# FPGA_QDRII.net
KiCad netlist of a schematic drawn in Altium Designer
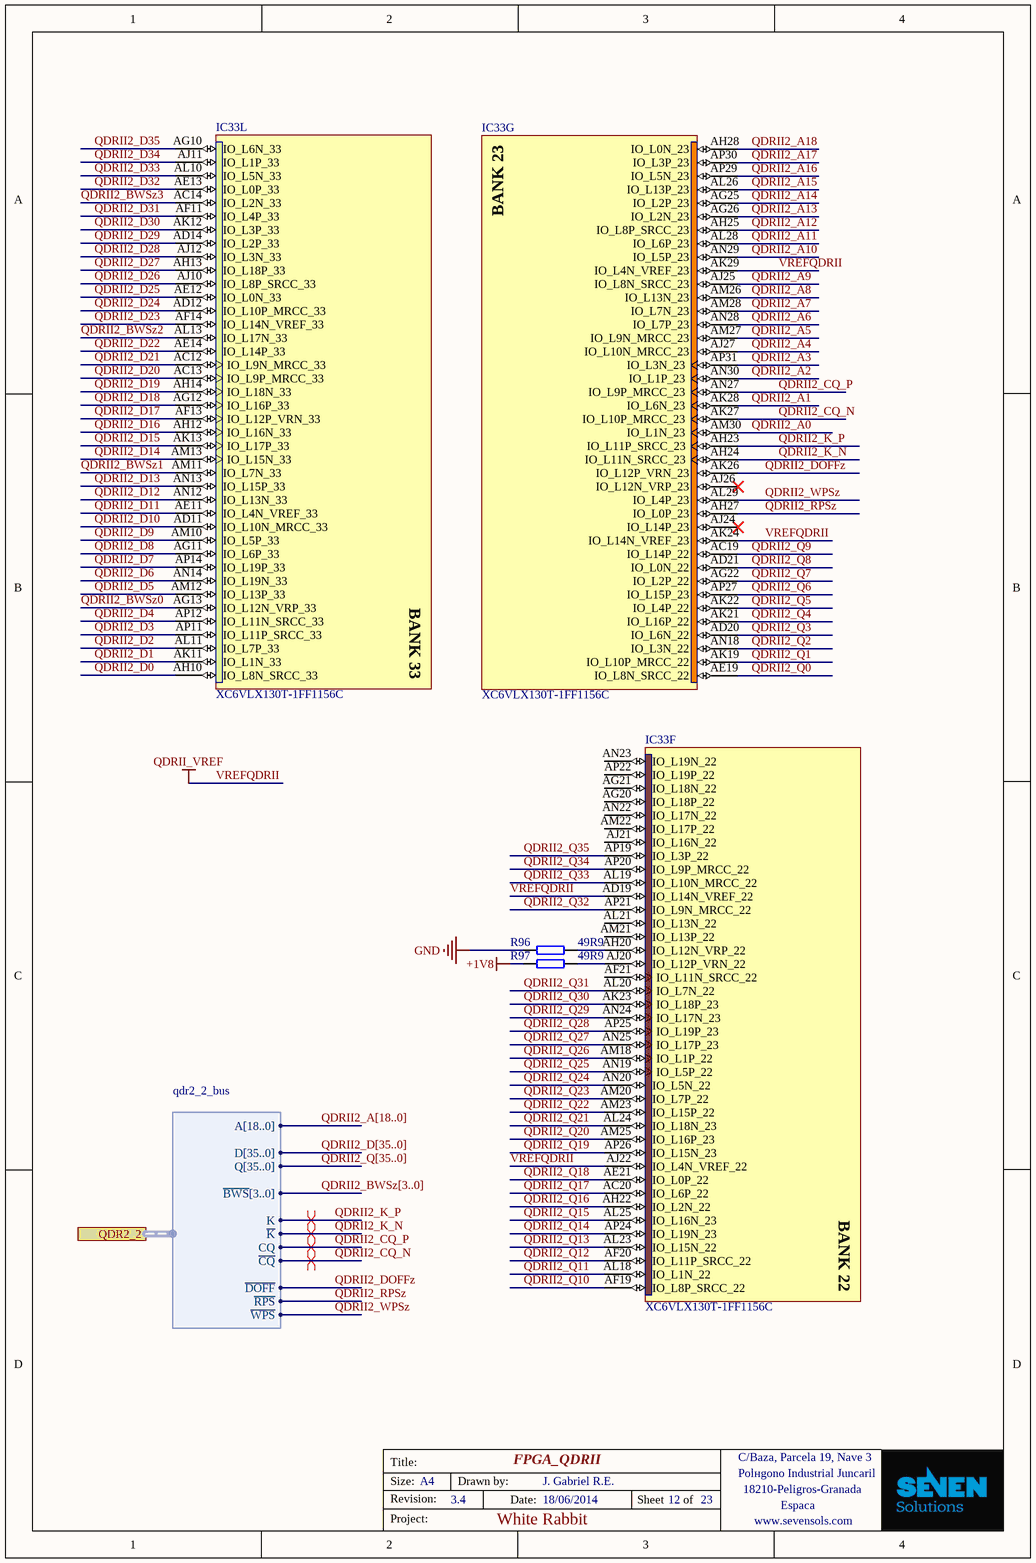
[diagram p0: FPGA_QDRII.SchDoc]

(export (version "E")
  (design (tool "Eeschema 10.0.6"))
  (components
    (comp (ref "IC33")
      (value "XC6VLX130T-1FF1156C")
      (footprint "FF1156")
      (fields (field (name "PUBLISHER") "Altium Limited"))
      (libsource (lib "Xilinx Virtex-6") (part "XC6VLX130T-1FF1156C"))
    )
    (comp (ref "R96")
      (value "49R9")
      (footprint "0402")
      (description "SMD Resistor")
      (fields (field (name "TOLERANCE") "±1%") (field (name "Comment") "49R9 (not mounted)"))
      (libsource (lib "wr_switch") (part "RES_SMD"))
    )
    (comp (ref "R97")
      (value "49R9")
      (footprint "0402")
      (description "SMD Resistor")
      (fields (field (name "TOLERANCE") "±1%") (field (name "Comment") "49R9 (not mounted)"))
      (libsource (lib "wr_switch") (part "RES_SMD"))
    )
  )
  (nets
    (net (code "2") (name "+1V8") (class "Default")
      (node (ref "R97") (pin "2") (pinfunction "2_2") (pintype "passive"))
    )
    (net (code "4") (name "/QDRII2_A0") (class "Default")
      (node (ref "IC33") (pin "AM30") (pinfunction "IO_L1N_23_AM30") (pintype "bidirectional"))
    )
    (net (code "5") (name "/QDRII2_A1") (class "Default")
      (node (ref "IC33") (pin "AK28") (pinfunction "IO_L6N_23_AK28") (pintype "bidirectional"))
    )
    (net (code "6") (name "/QDRII2_A2") (class "Default")
      (node (ref "IC33") (pin "AN30") (pinfunction "IO_L1P_23_AN30") (pintype "bidirectional"))
    )
    (net (code "7") (name "/QDRII2_A3") (class "Default")
      (node (ref "IC33") (pin "AP31") (pinfunction "IO_L3N_23_AP31") (pintype "bidirectional"))
    )
    (net (code "8") (name "/QDRII2_A4") (class "Default")
      (node (ref "IC33") (pin "AJ27") (pinfunction "IO_L10N_MRCC_23_AJ27") (pintype "bidirectional"))
    )
    (net (code "9") (name "/QDRII2_A5") (class "Default")
      (node (ref "IC33") (pin "AM27") (pinfunction "IO_L9N_MRCC_23_AM27") (pintype "bidirectional"))
    )
    (net (code "10") (name "/QDRII2_A6") (class "Default")
      (node (ref "IC33") (pin "AN28") (pinfunction "IO_L7P_23_AN28") (pintype "bidirectional"))
    )
    (net (code "11") (name "/QDRII2_A7") (class "Default")
      (node (ref "IC33") (pin "AM28") (pinfunction "IO_L7N_23_AM28") (pintype "bidirectional"))
    )
    (net (code "12") (name "/QDRII2_A8") (class "Default")
      (node (ref "IC33") (pin "AM26") (pinfunction "IO_L13N_23_AM26") (pintype "bidirectional"))
    )
    (net (code "13") (name "/QDRII2_A9") (class "Default")
      (node (ref "IC33") (pin "AJ25") (pinfunction "IO_L8N_SRCC_23_AJ25") (pintype "bidirectional"))
    )
    (net (code "14") (name "/QDRII2_A10") (class "Default")
      (node (ref "IC33") (pin "AN29") (pinfunction "IO_L5P_23_AN29") (pintype "bidirectional"))
    )
    (net (code "15") (name "/QDRII2_A11") (class "Default")
      (node (ref "IC33") (pin "AL28") (pinfunction "IO_L6P_23_AL28") (pintype "bidirectional"))
    )
    (net (code "16") (name "/QDRII2_A12") (class "Default")
      (node (ref "IC33") (pin "AH25") (pinfunction "IO_L8P_SRCC_23_AH25") (pintype "bidirectional"))
    )
    (net (code "17") (name "/QDRII2_A13") (class "Default")
      (node (ref "IC33") (pin "AG26") (pinfunction "IO_L2N_23_AG26") (pintype "bidirectional"))
    )
    (net (code "18") (name "/QDRII2_A14") (class "Default")
      (node (ref "IC33") (pin "AG25") (pinfunction "IO_L2P_23_AG25") (pintype "bidirectional"))
    )
    (net (code "19") (name "/QDRII2_A15") (class "Default")
      (node (ref "IC33") (pin "AL26") (pinfunction "IO_L13P_23_AL26") (pintype "bidirectional"))
    )
    (net (code "20") (name "/QDRII2_A16") (class "Default")
      (node (ref "IC33") (pin "AP29") (pinfunction "IO_L5N_23_AP29") (pintype "bidirectional"))
    )
    (net (code "21") (name "/QDRII2_A17") (class "Default")
      (node (ref "IC33") (pin "AP30") (pinfunction "IO_L3P_23_AP30") (pintype "bidirectional"))
    )
    (net (code "22") (name "/QDRII2_A18") (class "Default")
      (node (ref "IC33") (pin "AH28") (pinfunction "IO_L0N_23_AH28") (pintype "bidirectional"))
    )
    (net (code "24") (name "/QDRII2_BWSz0") (class "Default")
      (node (ref "IC33") (pin "AG13") (pinfunction "IO_L12N_VRP_33_AG13") (pintype "bidirectional"))
    )
    (net (code "25") (name "/QDRII2_BWSz1") (class "Default")
      (node (ref "IC33") (pin "AM11") (pinfunction "IO_L7N_33_AM11") (pintype "bidirectional"))
    )
    (net (code "26") (name "/QDRII2_BWSz2") (class "Default")
      (node (ref "IC33") (pin "AL13") (pinfunction "IO_L17N_33_AL13") (pintype "bidirectional"))
    )
    (net (code "27") (name "/QDRII2_BWSz3") (class "Default")
      (node (ref "IC33") (pin "AC14") (pinfunction "IO_L2N_33_AC14") (pintype "bidirectional"))
    )
    (net (code "28") (name "/QDRII2_CQ_N") (class "Default")
      (node (ref "IC33") (pin "AK27") (pinfunction "IO_L10P_MRCC_23_AK27") (pintype "bidirectional"))
    )
    (net (code "29") (name "/QDRII2_CQ_P") (class "Default")
      (node (ref "IC33") (pin "AN27") (pinfunction "IO_L9P_MRCC_23_AN27") (pintype "bidirectional"))
    )
    (net (code "30") (name "/QDRII2_D0") (class "Default")
      (node (ref "IC33") (pin "AH10") (pinfunction "IO_L8N_SRCC_33_AH10") (pintype "bidirectional"))
    )
    (net (code "31") (name "/QDRII2_D1") (class "Default")
      (node (ref "IC33") (pin "AK11") (pinfunction "IO_L1N_33_AK11") (pintype "bidirectional"))
    )
    (net (code "32") (name "/QDRII2_D2") (class "Default")
      (node (ref "IC33") (pin "AL11") (pinfunction "IO_L7P_33_AL11") (pintype "bidirectional"))
    )
    (net (code "33") (name "/QDRII2_D3") (class "Default")
      (node (ref "IC33") (pin "AP11") (pinfunction "IO_L11P_SRCC_33_AP11") (pintype "bidirectional"))
    )
    (net (code "34") (name "/QDRII2_D4") (class "Default")
      (node (ref "IC33") (pin "AP12") (pinfunction "IO_L11N_SRCC_33_AP12") (pintype "bidirectional"))
    )
    (net (code "35") (name "/QDRII2_D5") (class "Default")
      (node (ref "IC33") (pin "AM12") (pinfunction "IO_L13P_33_AM12") (pintype "bidirectional"))
    )
    (net (code "36") (name "/QDRII2_D6") (class "Default")
      (node (ref "IC33") (pin "AN14") (pinfunction "IO_L19N_33_AN14") (pintype "bidirectional"))
    )
    (net (code "37") (name "/QDRII2_D7") (class "Default")
      (node (ref "IC33") (pin "AP14") (pinfunction "IO_L19P_33_AP14") (pintype "bidirectional"))
    )
    (net (code "38") (name "/QDRII2_D8") (class "Default")
      (node (ref "IC33") (pin "AG11") (pinfunction "IO_L6P_33_AG11") (pintype "bidirectional"))
    )
    (net (code "39") (name "/QDRII2_D9") (class "Default")
      (node (ref "IC33") (pin "AM10") (pinfunction "IO_L5P_33_AM10") (pintype "bidirectional"))
    )
    (net (code "40") (name "/QDRII2_D10") (class "Default")
      (node (ref "IC33") (pin "AD11") (pinfunction "IO_L10N_MRCC_33_AD11") (pintype "bidirectional"))
    )
    (net (code "41") (name "/QDRII2_D11") (class "Default")
      (node (ref "IC33") (pin "AE11") (pinfunction "IO_L4N_VREF_33_AE11") (pintype "bidirectional"))
    )
    (net (code "42") (name "/QDRII2_D12") (class "Default")
      (node (ref "IC33") (pin "AN12") (pinfunction "IO_L13N_33_AN12") (pintype "bidirectional"))
    )
    (net (code "43") (name "/QDRII2_D13") (class "Default")
      (node (ref "IC33") (pin "AN13") (pinfunction "IO_L15P_33_AN13") (pintype "bidirectional"))
    )
    (net (code "44") (name "/QDRII2_D14") (class "Default")
      (node (ref "IC33") (pin "AM13") (pinfunction "IO_L15N_33_AM13") (pintype "bidirectional"))
    )
    (net (code "45") (name "/QDRII2_D15") (class "Default")
      (node (ref "IC33") (pin "AK13") (pinfunction "IO_L17P_33_AK13") (pintype "bidirectional"))
    )
    (net (code "46") (name "/QDRII2_D16") (class "Default")
      (node (ref "IC33") (pin "AH12") (pinfunction "IO_L16N_33_AH12") (pintype "bidirectional"))
    )
    (net (code "47") (name "/QDRII2_D17") (class "Default")
      (node (ref "IC33") (pin "AF13") (pinfunction "IO_L12P_VRN_33_AF13") (pintype "bidirectional"))
    )
    (net (code "48") (name "/QDRII2_D18") (class "Default")
      (node (ref "IC33") (pin "AG12") (pinfunction "IO_L16P_33_AG12") (pintype "bidirectional"))
    )
    (net (code "49") (name "/QDRII2_D19") (class "Default")
      (node (ref "IC33") (pin "AH14") (pinfunction "IO_L18N_33_AH14") (pintype "bidirectional"))
    )
    (net (code "50") (name "/QDRII2_D20") (class "Default")
      (node (ref "IC33") (pin "AC13") (pinfunction "IO_L9P_MRCC_33_AC13") (pintype "bidirectional"))
    )
    (net (code "51") (name "/QDRII2_D21") (class "Default")
      (node (ref "IC33") (pin "AC12") (pinfunction "IO_L9N_MRCC_33_AC12") (pintype "bidirectional"))
    )
    (net (code "52") (name "/QDRII2_D22") (class "Default")
      (node (ref "IC33") (pin "AE14") (pinfunction "IO_L14P_33_AE14") (pintype "bidirectional"))
    )
    (net (code "53") (name "/QDRII2_D23") (class "Default")
      (node (ref "IC33") (pin "AF14") (pinfunction "IO_L14N_VREF_33_AF14") (pintype "bidirectional"))
    )
    (net (code "54") (name "/QDRII2_D24") (class "Default")
      (node (ref "IC33") (pin "AD12") (pinfunction "IO_L10P_MRCC_33_AD12") (pintype "bidirectional"))
    )
    (net (code "55") (name "/QDRII2_D25") (class "Default")
      (node (ref "IC33") (pin "AE12") (pinfunction "IO_L0N_33_AE12") (pintype "bidirectional"))
    )
    (net (code "56") (name "/QDRII2_D26") (class "Default")
      (node (ref "IC33") (pin "AJ10") (pinfunction "IO_L8P_SRCC_33_AJ10") (pintype "bidirectional"))
    )
    (net (code "57") (name "/QDRII2_D27") (class "Default")
      (node (ref "IC33") (pin "AH13") (pinfunction "IO_L18P_33_AH13") (pintype "bidirectional"))
    )
    (net (code "58") (name "/QDRII2_D28") (class "Default")
      (node (ref "IC33") (pin "AJ12") (pinfunction "IO_L3N_33_AJ12") (pintype "bidirectional"))
    )
    (net (code "59") (name "/QDRII2_D29") (class "Default")
      (node (ref "IC33") (pin "AD14") (pinfunction "IO_L2P_33_AD14") (pintype "bidirectional"))
    )
    (net (code "60") (name "/QDRII2_D30") (class "Default")
      (node (ref "IC33") (pin "AK12") (pinfunction "IO_L3P_33_AK12") (pintype "bidirectional"))
    )
    (net (code "61") (name "/QDRII2_D31") (class "Default")
      (node (ref "IC33") (pin "AF11") (pinfunction "IO_L4P_33_AF11") (pintype "bidirectional"))
    )
    (net (code "62") (name "/QDRII2_D32") (class "Default")
      (node (ref "IC33") (pin "AE13") (pinfunction "IO_L0P_33_AE13") (pintype "bidirectional"))
    )
    (net (code "63") (name "/QDRII2_D33") (class "Default")
      (node (ref "IC33") (pin "AL10") (pinfunction "IO_L5N_33_AL10") (pintype "bidirectional"))
    )
    (net (code "64") (name "/QDRII2_D34") (class "Default")
      (node (ref "IC33") (pin "AJ11") (pinfunction "IO_L1P_33_AJ11") (pintype "bidirectional"))
    )
    (net (code "65") (name "/QDRII2_D35") (class "Default")
      (node (ref "IC33") (pin "AG10") (pinfunction "IO_L6N_33_AG10") (pintype "bidirectional"))
    )
    (net (code "66") (name "/QDRII2_DOFFz") (class "Default")
      (node (ref "IC33") (pin "AK26") (pinfunction "IO_L12P_VRN_23_AK26") (pintype "bidirectional"))
    )
    (net (code "68") (name "/QDRII2_K_N") (class "Default")
      (node (ref "IC33") (pin "AH24") (pinfunction "IO_L11N_SRCC_23_AH24") (pintype "bidirectional"))
    )
    (net (code "69") (name "/QDRII2_K_P") (class "Default")
      (node (ref "IC33") (pin "AH23") (pinfunction "IO_L11P_SRCC_23_AH23") (pintype "bidirectional"))
    )
    (net (code "70") (name "/QDRII2_Q0") (class "Default")
      (node (ref "IC33") (pin "AE19") (pinfunction "IO_L8N_SRCC_22_AE19") (pintype "bidirectional"))
    )
    (net (code "71") (name "/QDRII2_Q1") (class "Default")
      (node (ref "IC33") (pin "AK19") (pinfunction "IO_L10P_MRCC_22_AK19") (pintype "bidirectional"))
    )
    (net (code "72") (name "/QDRII2_Q2") (class "Default")
      (node (ref "IC33") (pin "AN18") (pinfunction "IO_L3N_22_AN18") (pintype "bidirectional"))
    )
    (net (code "73") (name "/QDRII2_Q3") (class "Default")
      (node (ref "IC33") (pin "AD20") (pinfunction "IO_L6N_22_AD20") (pintype "bidirectional"))
    )
    (net (code "74") (name "/QDRII2_Q4") (class "Default")
      (node (ref "IC33") (pin "AK21") (pinfunction "IO_L16P_22_AK21") (pintype "bidirectional"))
    )
    (net (code "75") (name "/QDRII2_Q5") (class "Default")
      (node (ref "IC33") (pin "AK22") (pinfunction "IO_L4P_22_AK22") (pintype "bidirectional"))
    )
    (net (code "76") (name "/QDRII2_Q6") (class "Default")
      (node (ref "IC33") (pin "AP27") (pinfunction "IO_L15P_23_AP27") (pintype "bidirectional"))
    )
    (net (code "77") (name "/QDRII2_Q7") (class "Default")
      (node (ref "IC33") (pin "AG22") (pinfunction "IO_L2P_22_AG22") (pintype "bidirectional"))
    )
    (net (code "78") (name "/QDRII2_Q8") (class "Default")
      (node (ref "IC33") (pin "AD21") (pinfunction "IO_L0N_22_AD21") (pintype "bidirectional"))
    )
    (net (code "79") (name "/QDRII2_Q9") (class "Default")
      (node (ref "IC33") (pin "AC19") (pinfunction "IO_L14P_22_AC19") (pintype "bidirectional"))
    )
    (net (code "80") (name "/QDRII2_Q10") (class "Default")
      (node (ref "IC33") (pin "AF19") (pinfunction "IO_L8P_SRCC_22_AF19") (pintype "bidirectional"))
    )
    (net (code "81") (name "/QDRII2_Q11") (class "Default")
      (node (ref "IC33") (pin "AL18") (pinfunction "IO_L1N_22_AL18") (pintype "bidirectional"))
    )
    (net (code "82") (name "/QDRII2_Q12") (class "Default")
      (node (ref "IC33") (pin "AF20") (pinfunction "IO_L11P_SRCC_22_AF20") (pintype "bidirectional"))
    )
    (net (code "83") (name "/QDRII2_Q13") (class "Default")
      (node (ref "IC33") (pin "AL23") (pinfunction "IO_L15N_22_AL23") (pintype "bidirectional"))
    )
    (net (code "84") (name "/QDRII2_Q14") (class "Default")
      (node (ref "IC33") (pin "AP24") (pinfunction "IO_L19N_23_AP24") (pintype "bidirectional"))
    )
    (net (code "85") (name "/QDRII2_Q15") (class "Default")
      (node (ref "IC33") (pin "AL25") (pinfunction "IO_L16N_23_AL25") (pintype "bidirectional"))
    )
    (net (code "86") (name "/QDRII2_Q16") (class "Default")
      (node (ref "IC33") (pin "AH22") (pinfunction "IO_L2N_22_AH22") (pintype "bidirectional"))
    )
    (net (code "87") (name "/QDRII2_Q17") (class "Default")
      (node (ref "IC33") (pin "AC20") (pinfunction "IO_L6P_22_AC20") (pintype "bidirectional"))
    )
    (net (code "88") (name "/QDRII2_Q18") (class "Default")
      (node (ref "IC33") (pin "AE21") (pinfunction "IO_L0P_22_AE21") (pintype "bidirectional"))
    )
    (net (code "89") (name "/QDRII2_Q19") (class "Default")
      (node (ref "IC33") (pin "AP26") (pinfunction "IO_L15N_23_AP26") (pintype "bidirectional"))
    )
    (net (code "90") (name "/QDRII2_Q20") (class "Default")
      (node (ref "IC33") (pin "AM25") (pinfunction "IO_L16P_23_AM25") (pintype "bidirectional"))
    )
    (net (code "91") (name "/QDRII2_Q21") (class "Default")
      (node (ref "IC33") (pin "AL24") (pinfunction "IO_L18N_23_AL24") (pintype "bidirectional"))
    )
    (net (code "92") (name "/QDRII2_Q22") (class "Default")
      (node (ref "IC33") (pin "AM23") (pinfunction "IO_L15P_22_AM23") (pintype "bidirectional"))
    )
    (net (code "93") (name "/QDRII2_Q23") (class "Default")
      (node (ref "IC33") (pin "AM20") (pinfunction "IO_L7P_22_AM20") (pintype "bidirectional"))
    )
    (net (code "94") (name "/QDRII2_Q24") (class "Default")
      (node (ref "IC33") (pin "AN20") (pinfunction "IO_L5N_22_AN20") (pintype "bidirectional"))
    )
    (net (code "95") (name "/QDRII2_Q25") (class "Default")
      (node (ref "IC33") (pin "AN19") (pinfunction "IO_L5P_22_AN19") (pintype "bidirectional"))
    )
    (net (code "96") (name "/QDRII2_Q26") (class "Default")
      (node (ref "IC33") (pin "AM18") (pinfunction "IO_L1P_22_AM18") (pintype "bidirectional"))
    )
    (net (code "97") (name "/QDRII2_Q27") (class "Default")
      (node (ref "IC33") (pin "AN25") (pinfunction "IO_L17P_23_AN25") (pintype "bidirectional"))
    )
    (net (code "98") (name "/QDRII2_Q28") (class "Default")
      (node (ref "IC33") (pin "AP25") (pinfunction "IO_L19P_23_AP25") (pintype "bidirectional"))
    )
    (net (code "99") (name "/QDRII2_Q29") (class "Default")
      (node (ref "IC33") (pin "AN24") (pinfunction "IO_L17N_23_AN24") (pintype "bidirectional"))
    )
    (net (code "100") (name "/QDRII2_Q30") (class "Default")
      (node (ref "IC33") (pin "AK23") (pinfunction "IO_L18P_23_AK23") (pintype "bidirectional"))
    )
    (net (code "101") (name "/QDRII2_Q31") (class "Default")
      (node (ref "IC33") (pin "AL20") (pinfunction "IO_L7N_22_AL20") (pintype "bidirectional"))
    )
    (net (code "102") (name "/QDRII2_Q32") (class "Default")
      (node (ref "IC33") (pin "AP21") (pinfunction "IO_L9N_MRCC_22_AP21") (pintype "bidirectional"))
    )
    (net (code "103") (name "/QDRII2_Q33") (class "Default")
      (node (ref "IC33") (pin "AL19") (pinfunction "IO_L10N_MRCC_22_AL19") (pintype "bidirectional"))
    )
    (net (code "104") (name "/QDRII2_Q34") (class "Default")
      (node (ref "IC33") (pin "AP20") (pinfunction "IO_L9P_MRCC_22_AP20") (pintype "bidirectional"))
    )
    (net (code "105") (name "/QDRII2_Q35") (class "Default")
      (node (ref "IC33") (pin "AP19") (pinfunction "IO_L3P_22_AP19") (pintype "bidirectional"))
    )
    (net (code "107") (name "/QDRII2_RPSz") (class "Default")
      (node (ref "IC33") (pin "AH27") (pinfunction "IO_L0P_23_AH27") (pintype "bidirectional"))
    )
    (net (code "108") (name "/QDRII2_WPSz") (class "Default")
      (node (ref "IC33") (pin "AL29") (pinfunction "IO_L4P_23_AL29") (pintype "bidirectional"))
    )
    (net (code "110") (name "GND") (class "Default")
      (node (ref "R96") (pin "2") (pinfunction "2_2") (pintype "passive"))
    )
    (net (code "111") (name "Net-(IC33F-IO_L12N_VRP_22)") (class "Default")
      (node (ref "IC33") (pin "AH20") (pinfunction "IO_L12N_VRP_22_AH20") (pintype "bidirectional"))
      (node (ref "R96") (pin "1") (pinfunction "1_1") (pintype "passive"))
    )
    (net (code "112") (name "Net-(IC33F-IO_L12P_VRN_22)") (class "Default")
      (node (ref "IC33") (pin "AJ20") (pinfunction "IO_L12P_VRN_22_AJ20") (pintype "bidirectional"))
      (node (ref "R97") (pin "1") (pinfunction "1_1") (pintype "passive"))
    )
    (net (code "113") (name "QDRII_VREF") (class "Default")
      (node (ref "IC33") (pin "AD19") (pinfunction "IO_L14N_VREF_22_AD19") (pintype "bidirectional"))
      (node (ref "IC33") (pin "AJ22") (pinfunction "IO_L4N_VREF_22_AJ22") (pintype "bidirectional"))
      (node (ref "IC33") (pin "AK24") (pinfunction "IO_L14N_VREF_23_AK24") (pintype "bidirectional"))
      (node (ref "IC33") (pin "AK29") (pinfunction "IO_L4N_VREF_23_AK29") (pintype "bidirectional"))
    )
    (net (code "114") (name "unconnected-(IC33F-IO_L11N_SRCC_22-PadAF21)") (class "Default")
      (node (ref "IC33") (pin "AF21") (pinfunction "IO_L11N_SRCC_22_AF21") (pintype "bidirectional"))
    )
    (net (code "115") (name "unconnected-(IC33F-IO_L13N_22-PadAL21)") (class "Default")
      (node (ref "IC33") (pin "AL21") (pinfunction "IO_L13N_22_AL21") (pintype "bidirectional"))
    )
    (net (code "116") (name "unconnected-(IC33F-IO_L13P_22-PadAM21)") (class "Default")
      (node (ref "IC33") (pin "AM21") (pinfunction "IO_L13P_22_AM21") (pintype "bidirectional"))
    )
    (net (code "117") (name "unconnected-(IC33F-IO_L16N_22-PadAJ21)") (class "Default")
      (node (ref "IC33") (pin "AJ21") (pinfunction "IO_L16N_22_AJ21") (pintype "bidirectional"))
    )
    (net (code "118") (name "unconnected-(IC33F-IO_L17N_22-PadAN22)") (class "Default")
      (node (ref "IC33") (pin "AN22") (pinfunction "IO_L17N_22_AN22") (pintype "bidirectional"))
    )
    (net (code "119") (name "unconnected-(IC33F-IO_L17P_22-PadAM22)") (class "Default")
      (node (ref "IC33") (pin "AM22") (pinfunction "IO_L17P_22_AM22") (pintype "bidirectional"))
    )
    (net (code "120") (name "unconnected-(IC33F-IO_L18N_22-PadAG21)") (class "Default")
      (node (ref "IC33") (pin "AG21") (pinfunction "IO_L18N_22_AG21") (pintype "bidirectional"))
    )
    (net (code "121") (name "unconnected-(IC33F-IO_L18P_22-PadAG20)") (class "Default")
      (node (ref "IC33") (pin "AG20") (pinfunction "IO_L18P_22_AG20") (pintype "bidirectional"))
    )
    (net (code "122") (name "unconnected-(IC33F-IO_L19N_22-PadAN23)") (class "Default")
      (node (ref "IC33") (pin "AN23") (pinfunction "IO_L19N_22_AN23") (pintype "bidirectional"))
    )
    (net (code "123") (name "unconnected-(IC33F-IO_L19P_22-PadAP22)") (class "Default")
      (node (ref "IC33") (pin "AP22") (pinfunction "IO_L19P_22_AP22") (pintype "bidirectional"))
    )
    (net (code "124") (name "unconnected-(IC33G-IO_L12N_VRP_23-PadAJ26)") (class "Default")
      (node (ref "IC33") (pin "AJ26") (pinfunction "IO_L12N_VRP_23_AJ26") (pintype "bidirectional+no_connect"))
    )
    (net (code "125") (name "unconnected-(IC33G-IO_L14P_23-PadAJ24)") (class "Default")
      (node (ref "IC33") (pin "AJ24") (pinfunction "IO_L14P_23_AJ24") (pintype "bidirectional+no_connect"))
    )
  )
)
